# schemathic.net
KiCad netlist of a schematic drawn in EAGLE
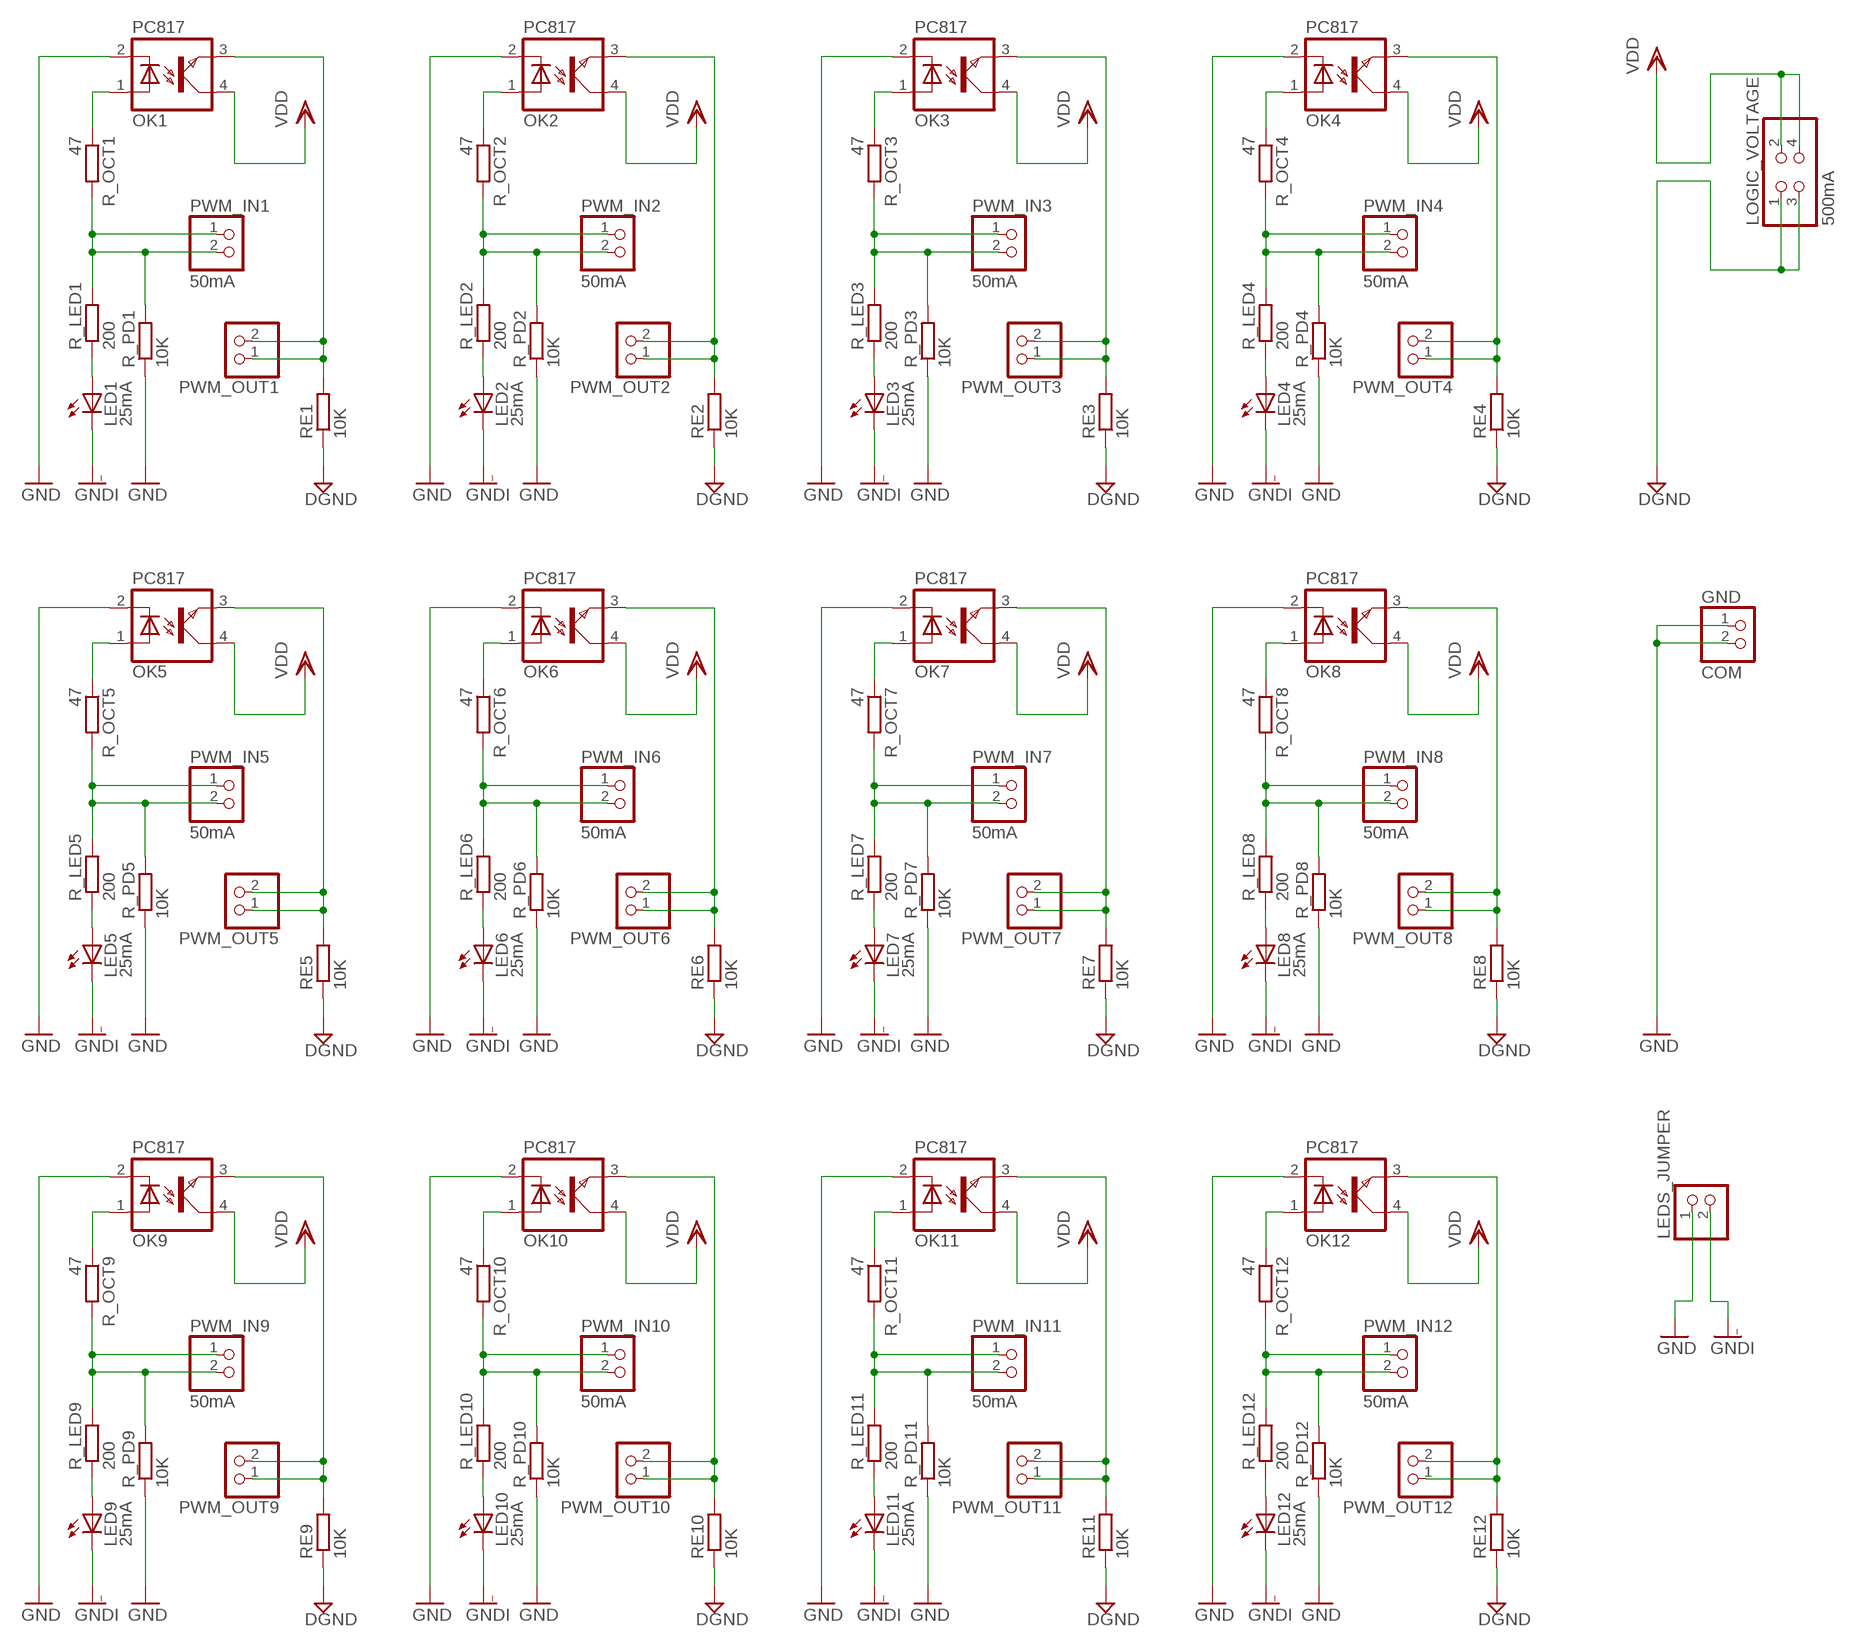
[diagram p0: schematic, sheet 1]

(export (version "E")
  (design (tool "Eeschema 10.0.6"))
  (components
    (comp (ref "GND")
      (value "COM")
      (footprint "eagle-import:1X02")
      (libsource (lib "eagle-import") (part "PINHD-1X2"))
    )
    (comp (ref "LED1")
      (value "25mA")
      (footprint "eagle-import:LED3MM")
      (libsource (lib "eagle-import") (part "LED3MM"))
    )
    (comp (ref "LED2")
      (value "25mA")
      (footprint "eagle-import:LED3MM")
      (libsource (lib "eagle-import") (part "LED3MM"))
    )
    (comp (ref "LED3")
      (value "25mA")
      (footprint "eagle-import:LED3MM")
      (libsource (lib "eagle-import") (part "LED3MM"))
    )
    (comp (ref "LED4")
      (value "25mA")
      (footprint "eagle-import:LED3MM")
      (libsource (lib "eagle-import") (part "LED3MM"))
    )
    (comp (ref "LED5")
      (value "25mA")
      (footprint "eagle-import:LED3MM")
      (libsource (lib "eagle-import") (part "LED3MM"))
    )
    (comp (ref "LED6")
      (value "25mA")
      (footprint "eagle-import:LED3MM")
      (libsource (lib "eagle-import") (part "LED3MM"))
    )
    (comp (ref "LED7")
      (value "25mA")
      (footprint "eagle-import:LED3MM")
      (libsource (lib "eagle-import") (part "LED3MM"))
    )
    (comp (ref "LED8")
      (value "25mA")
      (footprint "eagle-import:LED3MM")
      (libsource (lib "eagle-import") (part "LED3MM"))
    )
    (comp (ref "LED9")
      (value "25mA")
      (footprint "eagle-import:LED3MM")
      (libsource (lib "eagle-import") (part "LED3MM"))
    )
    (comp (ref "LED10")
      (value "25mA")
      (footprint "eagle-import:LED3MM")
      (libsource (lib "eagle-import") (part "LED3MM"))
    )
    (comp (ref "LED11")
      (value "25mA")
      (footprint "eagle-import:LED3MM")
      (libsource (lib "eagle-import") (part "LED3MM"))
    )
    (comp (ref "LED12")
      (value "25mA")
      (footprint "eagle-import:LED3MM")
      (libsource (lib "eagle-import") (part "LED3MM"))
    )
    (comp (ref "LEDS_JUMPER")
      (value "PINHD-1X2")
      (footprint "eagle-import:1X02")
      (libsource (lib "eagle-import") (part "PINHD-1X2"))
    )
    (comp (ref "LOGIC_VOLTAGE")
      (value "500mA")
      (footprint "eagle-import:2X02")
      (libsource (lib "eagle-import") (part "PINHD-2X2"))
    )
    (comp (ref "OK1")
      (value "PC817")
      (footprint "eagle-import:DIL04")
      (fields (field (name "MPN") "PC817X4J000F"))
      (libsource (lib "eagle-import") (part "PC817"))
    )
    (comp (ref "OK2")
      (value "PC817")
      (footprint "eagle-import:DIL04")
      (fields (field (name "MPN") "PC817X4J000F"))
      (libsource (lib "eagle-import") (part "PC817"))
    )
    (comp (ref "OK3")
      (value "PC817")
      (footprint "eagle-import:DIL04")
      (fields (field (name "MPN") "PC817X4J000F"))
      (libsource (lib "eagle-import") (part "PC817"))
    )
    (comp (ref "OK4")
      (value "PC817")
      (footprint "eagle-import:DIL04")
      (fields (field (name "MPN") "PC817X4J000F"))
      (libsource (lib "eagle-import") (part "PC817"))
    )
    (comp (ref "OK5")
      (value "PC817")
      (footprint "eagle-import:DIL04")
      (fields (field (name "MPN") "PC817X4J000F"))
      (libsource (lib "eagle-import") (part "PC817"))
    )
    (comp (ref "OK6")
      (value "PC817")
      (footprint "eagle-import:DIL04")
      (fields (field (name "MPN") "PC817X4J000F"))
      (libsource (lib "eagle-import") (part "PC817"))
    )
    (comp (ref "OK7")
      (value "PC817")
      (footprint "eagle-import:DIL04")
      (fields (field (name "MPN") "PC817X4J000F"))
      (libsource (lib "eagle-import") (part "PC817"))
    )
    (comp (ref "OK8")
      (value "PC817")
      (footprint "eagle-import:DIL04")
      (fields (field (name "MPN") "PC817X4J000F"))
      (libsource (lib "eagle-import") (part "PC817"))
    )
    (comp (ref "OK9")
      (value "PC817")
      (footprint "eagle-import:DIL04")
      (fields (field (name "MPN") "PC817X4J000F"))
      (libsource (lib "eagle-import") (part "PC817"))
    )
    (comp (ref "OK10")
      (value "PC817")
      (footprint "eagle-import:DIL04")
      (fields (field (name "MPN") "PC817X4J000F"))
      (libsource (lib "eagle-import") (part "PC817"))
    )
    (comp (ref "OK11")
      (value "PC817")
      (footprint "eagle-import:DIL04")
      (fields (field (name "MPN") "PC817X4J000F"))
      (libsource (lib "eagle-import") (part "PC817"))
    )
    (comp (ref "OK12")
      (value "PC817")
      (footprint "eagle-import:DIL04")
      (fields (field (name "MPN") "PC817X4J000F"))
      (libsource (lib "eagle-import") (part "PC817"))
    )
    (comp (ref "PWM_IN1")
      (value "50mA")
      (footprint "eagle-import:1X02")
      (libsource (lib "eagle-import") (part "PINHD-1X2"))
    )
    (comp (ref "PWM_IN2")
      (value "50mA")
      (footprint "eagle-import:1X02")
      (libsource (lib "eagle-import") (part "PINHD-1X2"))
    )
    (comp (ref "PWM_IN3")
      (value "50mA")
      (footprint "eagle-import:1X02")
      (libsource (lib "eagle-import") (part "PINHD-1X2"))
    )
    (comp (ref "PWM_IN4")
      (value "50mA")
      (footprint "eagle-import:1X02")
      (libsource (lib "eagle-import") (part "PINHD-1X2"))
    )
    (comp (ref "PWM_IN5")
      (value "50mA")
      (footprint "eagle-import:1X02")
      (libsource (lib "eagle-import") (part "PINHD-1X2"))
    )
    (comp (ref "PWM_IN6")
      (value "50mA")
      (footprint "eagle-import:1X02")
      (libsource (lib "eagle-import") (part "PINHD-1X2"))
    )
    (comp (ref "PWM_IN7")
      (value "50mA")
      (footprint "eagle-import:1X02")
      (libsource (lib "eagle-import") (part "PINHD-1X2"))
    )
    (comp (ref "PWM_IN8")
      (value "50mA")
      (footprint "eagle-import:1X02")
      (libsource (lib "eagle-import") (part "PINHD-1X2"))
    )
    (comp (ref "PWM_IN9")
      (value "50mA")
      (footprint "eagle-import:1X02")
      (libsource (lib "eagle-import") (part "PINHD-1X2"))
    )
    (comp (ref "PWM_IN10")
      (value "50mA")
      (footprint "eagle-import:1X02")
      (libsource (lib "eagle-import") (part "PINHD-1X2"))
    )
    (comp (ref "PWM_IN11")
      (value "50mA")
      (footprint "eagle-import:1X02")
      (libsource (lib "eagle-import") (part "PINHD-1X2"))
    )
    (comp (ref "PWM_IN12")
      (value "50mA")
      (footprint "eagle-import:1X02")
      (libsource (lib "eagle-import") (part "PINHD-1X2"))
    )
    (comp (ref "PWM_OUT1")
      (value "PINHD-1X2")
      (footprint "eagle-import:1X02")
      (libsource (lib "eagle-import") (part "PINHD-1X2"))
    )
    (comp (ref "PWM_OUT2")
      (value "PINHD-1X2")
      (footprint "eagle-import:1X02")
      (libsource (lib "eagle-import") (part "PINHD-1X2"))
    )
    (comp (ref "PWM_OUT3")
      (value "PINHD-1X2")
      (footprint "eagle-import:1X02")
      (libsource (lib "eagle-import") (part "PINHD-1X2"))
    )
    (comp (ref "PWM_OUT4")
      (value "PINHD-1X2")
      (footprint "eagle-import:1X02")
      (libsource (lib "eagle-import") (part "PINHD-1X2"))
    )
    (comp (ref "PWM_OUT5")
      (value "PINHD-1X2")
      (footprint "eagle-import:1X02")
      (libsource (lib "eagle-import") (part "PINHD-1X2"))
    )
    (comp (ref "PWM_OUT6")
      (value "PINHD-1X2")
      (footprint "eagle-import:1X02")
      (libsource (lib "eagle-import") (part "PINHD-1X2"))
    )
    (comp (ref "PWM_OUT7")
      (value "PINHD-1X2")
      (footprint "eagle-import:1X02")
      (libsource (lib "eagle-import") (part "PINHD-1X2"))
    )
    (comp (ref "PWM_OUT8")
      (value "PINHD-1X2")
      (footprint "eagle-import:1X02")
      (libsource (lib "eagle-import") (part "PINHD-1X2"))
    )
    (comp (ref "PWM_OUT9")
      (value "PINHD-1X2")
      (footprint "eagle-import:1X02")
      (libsource (lib "eagle-import") (part "PINHD-1X2"))
    )
    (comp (ref "PWM_OUT10")
      (value "PINHD-1X2")
      (footprint "eagle-import:1X02")
      (libsource (lib "eagle-import") (part "PINHD-1X2"))
    )
    (comp (ref "PWM_OUT11")
      (value "PINHD-1X2")
      (footprint "eagle-import:1X02")
      (libsource (lib "eagle-import") (part "PINHD-1X2"))
    )
    (comp (ref "PWM_OUT12")
      (value "PINHD-1X2")
      (footprint "eagle-import:1X02")
      (libsource (lib "eagle-import") (part "PINHD-1X2"))
    )
    (comp (ref "RE1")
      (value "10K")
      (footprint "eagle-import:0204_7")
      (libsource (lib "eagle-import") (part "R-EU_0204/7"))
    )
    (comp (ref "RE2")
      (value "10K")
      (footprint "eagle-import:0204_7")
      (libsource (lib "eagle-import") (part "R-EU_0204/7"))
    )
    (comp (ref "RE3")
      (value "10K")
      (footprint "eagle-import:0204_7")
      (libsource (lib "eagle-import") (part "R-EU_0204/7"))
    )
    (comp (ref "RE4")
      (value "10K")
      (footprint "eagle-import:0204_7")
      (libsource (lib "eagle-import") (part "R-EU_0204/7"))
    )
    (comp (ref "RE5")
      (value "10K")
      (footprint "eagle-import:0204_7")
      (libsource (lib "eagle-import") (part "R-EU_0204/7"))
    )
    (comp (ref "RE6")
      (value "10K")
      (footprint "eagle-import:0204_7")
      (libsource (lib "eagle-import") (part "R-EU_0204/7"))
    )
    (comp (ref "RE7")
      (value "10K")
      (footprint "eagle-import:0204_7")
      (libsource (lib "eagle-import") (part "R-EU_0204/7"))
    )
    (comp (ref "RE8")
      (value "10K")
      (footprint "eagle-import:0204_7")
      (libsource (lib "eagle-import") (part "R-EU_0204/7"))
    )
    (comp (ref "RE9")
      (value "10K")
      (footprint "eagle-import:0204_7")
      (libsource (lib "eagle-import") (part "R-EU_0204/7"))
    )
    (comp (ref "RE10")
      (value "10K")
      (footprint "eagle-import:0204_7")
      (libsource (lib "eagle-import") (part "R-EU_0204/7"))
    )
    (comp (ref "RE11")
      (value "10K")
      (footprint "eagle-import:0204_7")
      (libsource (lib "eagle-import") (part "R-EU_0204/7"))
    )
    (comp (ref "RE12")
      (value "10K")
      (footprint "eagle-import:0204_7")
      (libsource (lib "eagle-import") (part "R-EU_0204/7"))
    )
    (comp (ref "R_LED1")
      (value "200")
      (footprint "eagle-import:0204_7")
      (libsource (lib "eagle-import") (part "R-EU_0204/7"))
    )
    (comp (ref "R_LED2")
      (value "200")
      (footprint "eagle-import:0204_7")
      (libsource (lib "eagle-import") (part "R-EU_0204/7"))
    )
    (comp (ref "R_LED3")
      (value "200")
      (footprint "eagle-import:0204_7")
      (libsource (lib "eagle-import") (part "R-EU_0204/7"))
    )
    (comp (ref "R_LED4")
      (value "200")
      (footprint "eagle-import:0204_7")
      (libsource (lib "eagle-import") (part "R-EU_0204/7"))
    )
    (comp (ref "R_LED5")
      (value "200")
      (footprint "eagle-import:0204_7")
      (libsource (lib "eagle-import") (part "R-EU_0204/7"))
    )
    (comp (ref "R_LED6")
      (value "200")
      (footprint "eagle-import:0204_7")
      (libsource (lib "eagle-import") (part "R-EU_0204/7"))
    )
    (comp (ref "R_LED7")
      (value "200")
      (footprint "eagle-import:0204_7")
      (libsource (lib "eagle-import") (part "R-EU_0204/7"))
    )
    (comp (ref "R_LED8")
      (value "200")
      (footprint "eagle-import:0204_7")
      (libsource (lib "eagle-import") (part "R-EU_0204/7"))
    )
    (comp (ref "R_LED9")
      (value "200")
      (footprint "eagle-import:0204_7")
      (libsource (lib "eagle-import") (part "R-EU_0204/7"))
    )
    (comp (ref "R_LED10")
      (value "200")
      (footprint "eagle-import:0204_7")
      (libsource (lib "eagle-import") (part "R-EU_0204/7"))
    )
    (comp (ref "R_LED11")
      (value "200")
      (footprint "eagle-import:0204_7")
      (libsource (lib "eagle-import") (part "R-EU_0204/7"))
    )
    (comp (ref "R_LED12")
      (value "200")
      (footprint "eagle-import:0204_7")
      (libsource (lib "eagle-import") (part "R-EU_0204/7"))
    )
    (comp (ref "R_OCT1")
      (value "47")
      (footprint "eagle-import:0204_7")
      (libsource (lib "eagle-import") (part "R-EU_0204/7"))
    )
    (comp (ref "R_OCT2")
      (value "47")
      (footprint "eagle-import:0204_7")
      (libsource (lib "eagle-import") (part "R-EU_0204/7"))
    )
    (comp (ref "R_OCT3")
      (value "47")
      (footprint "eagle-import:0204_7")
      (libsource (lib "eagle-import") (part "R-EU_0204/7"))
    )
    (comp (ref "R_OCT4")
      (value "47")
      (footprint "eagle-import:0204_7")
      (libsource (lib "eagle-import") (part "R-EU_0204/7"))
    )
    (comp (ref "R_OCT5")
      (value "47")
      (footprint "eagle-import:0204_7")
      (libsource (lib "eagle-import") (part "R-EU_0204/7"))
    )
    (comp (ref "R_OCT6")
      (value "47")
      (footprint "eagle-import:0204_7")
      (libsource (lib "eagle-import") (part "R-EU_0204/7"))
    )
    (comp (ref "R_OCT7")
      (value "47")
      (footprint "eagle-import:0204_7")
      (libsource (lib "eagle-import") (part "R-EU_0204/7"))
    )
    (comp (ref "R_OCT8")
      (value "47")
      (footprint "eagle-import:0204_7")
      (libsource (lib "eagle-import") (part "R-EU_0204/7"))
    )
    (comp (ref "R_OCT9")
      (value "47")
      (footprint "eagle-import:0204_7")
      (libsource (lib "eagle-import") (part "R-EU_0204/7"))
    )
    (comp (ref "R_OCT10")
      (value "47")
      (footprint "eagle-import:0204_7")
      (libsource (lib "eagle-import") (part "R-EU_0204/7"))
    )
    (comp (ref "R_OCT11")
      (value "47")
      (footprint "eagle-import:0204_7")
      (libsource (lib "eagle-import") (part "R-EU_0204/7"))
    )
    (comp (ref "R_OCT12")
      (value "47")
      (footprint "eagle-import:0204_7")
      (libsource (lib "eagle-import") (part "R-EU_0204/7"))
    )
    (comp (ref "R_PD1")
      (value "10K")
      (footprint "eagle-import:0204_7")
      (libsource (lib "eagle-import") (part "R-EU_0204/7"))
    )
    (comp (ref "R_PD2")
      (value "10K")
      (footprint "eagle-import:0204_7")
      (libsource (lib "eagle-import") (part "R-EU_0204/7"))
    )
    (comp (ref "R_PD3")
      (value "10K")
      (footprint "eagle-import:0204_7")
      (libsource (lib "eagle-import") (part "R-EU_0204/7"))
    )
    (comp (ref "R_PD4")
      (value "10K")
      (footprint "eagle-import:0204_7")
      (libsource (lib "eagle-import") (part "R-EU_0204/7"))
    )
    (comp (ref "R_PD5")
      (value "10K")
      (footprint "eagle-import:0204_7")
      (libsource (lib "eagle-import") (part "R-EU_0204/7"))
    )
    (comp (ref "R_PD6")
      (value "10K")
      (footprint "eagle-import:0204_7")
      (libsource (lib "eagle-import") (part "R-EU_0204/7"))
    )
    (comp (ref "R_PD7")
      (value "10K")
      (footprint "eagle-import:0204_7")
      (libsource (lib "eagle-import") (part "R-EU_0204/7"))
    )
    (comp (ref "R_PD8")
      (value "10K")
      (footprint "eagle-import:0204_7")
      (libsource (lib "eagle-import") (part "R-EU_0204/7"))
    )
    (comp (ref "R_PD9")
      (value "10K")
      (footprint "eagle-import:0204_7")
      (libsource (lib "eagle-import") (part "R-EU_0204/7"))
    )
    (comp (ref "R_PD10")
      (value "10K")
      (footprint "eagle-import:0204_7")
      (libsource (lib "eagle-import") (part "R-EU_0204/7"))
    )
    (comp (ref "R_PD11")
      (value "10K")
      (footprint "eagle-import:0204_7")
      (libsource (lib "eagle-import") (part "R-EU_0204/7"))
    )
    (comp (ref "R_PD12")
      (value "10K")
      (footprint "eagle-import:0204_7")
      (libsource (lib "eagle-import") (part "R-EU_0204/7"))
    )
  )
  (nets
    (net (code "1") (name "DGND") (class "Default")
      (node (ref "LOGIC_VOLTAGE") (pin "1") (pinfunction "1_1") (pintype "passive"))
      (node (ref "LOGIC_VOLTAGE") (pin "3") (pinfunction "3_3") (pintype "passive"))
      (node (ref "RE1") (pin "1") (pinfunction "1_1") (pintype "passive"))
      (node (ref "RE10") (pin "1") (pinfunction "1_1") (pintype "passive"))
      (node (ref "RE11") (pin "1") (pinfunction "1_1") (pintype "passive"))
      (node (ref "RE12") (pin "1") (pinfunction "1_1") (pintype "passive"))
      (node (ref "RE2") (pin "1") (pinfunction "1_1") (pintype "passive"))
      (node (ref "RE3") (pin "1") (pinfunction "1_1") (pintype "passive"))
      (node (ref "RE4") (pin "1") (pinfunction "1_1") (pintype "passive"))
      (node (ref "RE5") (pin "1") (pinfunction "1_1") (pintype "passive"))
      (node (ref "RE6") (pin "1") (pinfunction "1_1") (pintype "passive"))
      (node (ref "RE7") (pin "1") (pinfunction "1_1") (pintype "passive"))
      (node (ref "RE8") (pin "1") (pinfunction "1_1") (pintype "passive"))
      (node (ref "RE9") (pin "1") (pinfunction "1_1") (pintype "passive"))
    )
    (net (code "2") (name "GND") (class "Default")
      (node (ref "GND") (pin "1") (pinfunction "1_1") (pintype "passive"))
      (node (ref "GND") (pin "2") (pinfunction "2_2") (pintype "passive"))
      (node (ref "LEDS_JUMPER") (pin "1") (pinfunction "1_1") (pintype "passive"))
      (node (ref "OK1") (pin "2") (pinfunction "C_2") (pintype "passive"))
      (node (ref "OK10") (pin "2") (pinfunction "C_2") (pintype "passive"))
      (node (ref "OK11") (pin "2") (pinfunction "C_2") (pintype "passive"))
      (node (ref "OK12") (pin "2") (pinfunction "C_2") (pintype "passive"))
      (node (ref "OK2") (pin "2") (pinfunction "C_2") (pintype "passive"))
      (node (ref "OK3") (pin "2") (pinfunction "C_2") (pintype "passive"))
      (node (ref "OK4") (pin "2") (pinfunction "C_2") (pintype "passive"))
      (node (ref "OK5") (pin "2") (pinfunction "C_2") (pintype "passive"))
      (node (ref "OK6") (pin "2") (pinfunction "C_2") (pintype "passive"))
      (node (ref "OK7") (pin "2") (pinfunction "C_2") (pintype "passive"))
      (node (ref "OK8") (pin "2") (pinfunction "C_2") (pintype "passive"))
      (node (ref "OK9") (pin "2") (pinfunction "C_2") (pintype "passive"))
      (node (ref "R_PD1") (pin "1") (pinfunction "1_1") (pintype "passive"))
      (node (ref "R_PD10") (pin "1") (pinfunction "1_1") (pintype "passive"))
      (node (ref "R_PD11") (pin "1") (pinfunction "1_1") (pintype "passive"))
      (node (ref "R_PD12") (pin "1") (pinfunction "1_1") (pintype "passive"))
      (node (ref "R_PD2") (pin "1") (pinfunction "1_1") (pintype "passive"))
      (node (ref "R_PD3") (pin "1") (pinfunction "1_1") (pintype "passive"))
      (node (ref "R_PD4") (pin "1") (pinfunction "1_1") (pintype "passive"))
      (node (ref "R_PD5") (pin "1") (pinfunction "1_1") (pintype "passive"))
      (node (ref "R_PD6") (pin "1") (pinfunction "1_1") (pintype "passive"))
      (node (ref "R_PD7") (pin "1") (pinfunction "1_1") (pintype "passive"))
      (node (ref "R_PD8") (pin "1") (pinfunction "1_1") (pintype "passive"))
      (node (ref "R_PD9") (pin "1") (pinfunction "1_1") (pintype "passive"))
    )
    (net (code "3") (name "GNDI") (class "Default")
      (node (ref "LED1") (pin "K") (pinfunction "C_K") (pintype "passive"))
      (node (ref "LED10") (pin "K") (pinfunction "C_K") (pintype "passive"))
      (node (ref "LED11") (pin "K") (pinfunction "C_K") (pintype "passive"))
      (node (ref "LED12") (pin "K") (pinfunction "C_K") (pintype "passive"))
      (node (ref "LED2") (pin "K") (pinfunction "C_K") (pintype "passive"))
      (node (ref "LED3") (pin "K") (pinfunction "C_K") (pintype "passive"))
      (node (ref "LED4") (pin "K") (pinfunction "C_K") (pintype "passive"))
      (node (ref "LED5") (pin "K") (pinfunction "C_K") (pintype "passive"))
      (node (ref "LED6") (pin "K") (pinfunction "C_K") (pintype "passive"))
      (node (ref "LED7") (pin "K") (pinfunction "C_K") (pintype "passive"))
      (node (ref "LED8") (pin "K") (pinfunction "C_K") (pintype "passive"))
      (node (ref "LED9") (pin "K") (pinfunction "C_K") (pintype "passive"))
      (node (ref "LEDS_JUMPER") (pin "2") (pinfunction "2_2") (pintype "passive"))
    )
    (net (code "4") (name "Net-(LED1-PadA)") (class "Default")
      (node (ref "LED1") (pin "A") (pinfunction "A_A") (pintype "passive"))
      (node (ref "R_LED1") (pin "1") (pinfunction "1_1") (pintype "passive"))
    )
    (net (code "5") (name "Net-(LED2-PadA)") (class "Default")
      (node (ref "LED2") (pin "A") (pinfunction "A_A") (pintype "passive"))
      (node (ref "R_LED2") (pin "1") (pinfunction "1_1") (pintype "passive"))
    )
    (net (code "6") (name "Net-(LED3-PadA)") (class "Default")
      (node (ref "LED3") (pin "A") (pinfunction "A_A") (pintype "passive"))
      (node (ref "R_LED3") (pin "1") (pinfunction "1_1") (pintype "passive"))
    )
    (net (code "7") (name "Net-(LED4-PadA)") (class "Default")
      (node (ref "LED4") (pin "A") (pinfunction "A_A") (pintype "passive"))
      (node (ref "R_LED4") (pin "1") (pinfunction "1_1") (pintype "passive"))
    )
    (net (code "8") (name "Net-(LED5-PadA)") (class "Default")
      (node (ref "LED5") (pin "A") (pinfunction "A_A") (pintype "passive"))
      (node (ref "R_LED5") (pin "1") (pinfunction "1_1") (pintype "passive"))
    )
    (net (code "9") (name "Net-(LED6-PadA)") (class "Default")
      (node (ref "LED6") (pin "A") (pinfunction "A_A") (pintype "passive"))
      (node (ref "R_LED6") (pin "1") (pinfunction "1_1") (pintype "passive"))
    )
    (net (code "10") (name "Net-(LED7-PadA)") (class "Default")
      (node (ref "LED7") (pin "A") (pinfunction "A_A") (pintype "passive"))
      (node (ref "R_LED7") (pin "1") (pinfunction "1_1") (pintype "passive"))
    )
    (net (code "11") (name "Net-(LED8-PadA)") (class "Default")
      (node (ref "LED8") (pin "A") (pinfunction "A_A") (pintype "passive"))
      (node (ref "R_LED8") (pin "1") (pinfunction "1_1") (pintype "passive"))
    )
    (net (code "12") (name "Net-(LED9-PadA)") (class "Default")
      (node (ref "LED9") (pin "A") (pinfunction "A_A") (pintype "passive"))
      (node (ref "R_LED9") (pin "1") (pinfunction "1_1") (pintype "passive"))
    )
    (net (code "13") (name "Net-(LED10-PadA)") (class "Default")
      (node (ref "LED10") (pin "A") (pinfunction "A_A") (pintype "passive"))
      (node (ref "R_LED10") (pin "1") (pinfunction "1_1") (pintype "passive"))
    )
    (net (code "14") (name "Net-(LED11-PadA)") (class "Default")
      (node (ref "LED11") (pin "A") (pinfunction "A_A") (pintype "passive"))
      (node (ref "R_LED11") (pin "1") (pinfunction "1_1") (pintype "passive"))
    )
    (net (code "15") (name "Net-(LED12-PadA)") (class "Default")
      (node (ref "LED12") (pin "A") (pinfunction "A_A") (pintype "passive"))
      (node (ref "R_LED12") (pin "1") (pinfunction "1_1") (pintype "passive"))
    )
    (net (code "16") (name "Net-(OK1-A)") (class "Default")
      (node (ref "OK1") (pin "1") (pinfunction "A_1") (pintype "passive"))
      (node (ref "R_OCT1") (pin "1") (pinfunction "1_1") (pintype "passive"))
    )
    (net (code "17") (name "Net-(OK1-EMIT)") (class "Default")
      (node (ref "OK1") (pin "3") (pinfunction "EMIT_3") (pintype "passive"))
      (node (ref "PWM_OUT1") (pin "1") (pinfunction "1_1") (pintype "passive"))
      (node (ref "PWM_OUT1") (pin "2") (pinfunction "2_2") (pintype "passive"))
      (node (ref "RE1") (pin "2") (pinfunction "2_2") (pintype "passive"))
    )
    (net (code "18") (name "Net-(OK2-A)") (class "Default")
      (node (ref "OK2") (pin "1") (pinfunction "A_1") (pintype "passive"))
      (node (ref "R_OCT2") (pin "1") (pinfunction "1_1") (pintype "passive"))
    )
    (net (code "19") (name "Net-(OK2-EMIT)") (class "Default")
      (node (ref "OK2") (pin "3") (pinfunction "EMIT_3") (pintype "passive"))
      (node (ref "PWM_OUT2") (pin "1") (pinfunction "1_1") (pintype "passive"))
      (node (ref "PWM_OUT2") (pin "2") (pinfunction "2_2") (pintype "passive"))
      (node (ref "RE2") (pin "2") (pinfunction "2_2") (pintype "passive"))
    )
    (net (code "20") (name "Net-(OK3-A)") (class "Default")
      (node (ref "OK3") (pin "1") (pinfunction "A_1") (pintype "passive"))
      (node (ref "R_OCT3") (pin "1") (pinfunction "1_1") (pintype "passive"))
    )
    (net (code "21") (name "Net-(OK3-EMIT)") (class "Default")
      (node (ref "OK3") (pin "3") (pinfunction "EMIT_3") (pintype "passive"))
      (node (ref "PWM_OUT3") (pin "1") (pinfunction "1_1") (pintype "passive"))
      (node (ref "PWM_OUT3") (pin "2") (pinfunction "2_2") (pintype "passive"))
      (node (ref "RE3") (pin "2") (pinfunction "2_2") (pintype "passive"))
    )
    (net (code "22") (name "Net-(OK4-A)") (class "Default")
      (node (ref "OK4") (pin "1") (pinfunction "A_1") (pintype "passive"))
      (node (ref "R_OCT4") (pin "1") (pinfunction "1_1") (pintype "passive"))
    )
    (net (code "23") (name "Net-(OK4-EMIT)") (class "Default")
      (node (ref "OK4") (pin "3") (pinfunction "EMIT_3") (pintype "passive"))
      (node (ref "PWM_OUT4") (pin "1") (pinfunction "1_1") (pintype "passive"))
      (node (ref "PWM_OUT4") (pin "2") (pinfunction "2_2") (pintype "passive"))
      (node (ref "RE4") (pin "2") (pinfunction "2_2") (pintype "passive"))
    )
    (net (code "24") (name "Net-(OK5-A)") (class "Default")
      (node (ref "OK5") (pin "1") (pinfunction "A_1") (pintype "passive"))
      (node (ref "R_OCT5") (pin "1") (pinfunction "1_1") (pintype "passive"))
    )
    (net (code "25") (name "Net-(OK5-EMIT)") (class "Default")
      (node (ref "OK5") (pin "3") (pinfunction "EMIT_3") (pintype "passive"))
      (node (ref "PWM_OUT5") (pin "1") (pinfunction "1_1") (pintype "passive"))
      (node (ref "PWM_OUT5") (pin "2") (pinfunction "2_2") (pintype "passive"))
      (node (ref "RE5") (pin "2") (pinfunction "2_2") (pintype "passive"))
    )
    (net (code "26") (name "Net-(OK6-A)") (class "Default")
      (node (ref "OK6") (pin "1") (pinfunction "A_1") (pintype "passive"))
      (node (ref "R_OCT6") (pin "1") (pinfunction "1_1") (pintype "passive"))
    )
    (net (code "27") (name "Net-(OK6-EMIT)") (class "Default")
      (node (ref "OK6") (pin "3") (pinfunction "EMIT_3") (pintype "passive"))
      (node (ref "PWM_OUT6") (pin "1") (pinfunction "1_1") (pintype "passive"))
      (node (ref "PWM_OUT6") (pin "2") (pinfunction "2_2") (pintype "passive"))
      (node (ref "RE6") (pin "2") (pinfunction "2_2") (pintype "passive"))
    )
    (net (code "28") (name "Net-(OK7-A)") (class "Default")
      (node (ref "OK7") (pin "1") (pinfunction "A_1") (pintype "passive"))
      (node (ref "R_OCT7") (pin "1") (pinfunction "1_1") (pintype "passive"))
    )
    (net (code "29") (name "Net-(OK7-EMIT)") (class "Default")
      (node (ref "OK7") (pin "3") (pinfunction "EMIT_3") (pintype "passive"))
      (node (ref "PWM_OUT7") (pin "1") (pinfunction "1_1") (pintype "passive"))
      (node (ref "PWM_OUT7") (pin "2") (pinfunction "2_2") (pintype "passive"))
      (node (ref "RE7") (pin "2") (pinfunction "2_2") (pintype "passive"))
    )
    (net (code "30") (name "Net-(OK8-A)") (class "Default")
      (node (ref "OK8") (pin "1") (pinfunction "A_1") (pintype "passive"))
      (node (ref "R_OCT8") (pin "1") (pinfunction "1_1") (pintype "passive"))
    )
    (net (code "31") (name "Net-(OK8-EMIT)") (class "Default")
      (node (ref "OK8") (pin "3") (pinfunction "EMIT_3") (pintype "passive"))
      (node (ref "PWM_OUT8") (pin "1") (pinfunction "1_1") (pintype "passive"))
      (node (ref "PWM_OUT8") (pin "2") (pinfunction "2_2") (pintype "passive"))
      (node (ref "RE8") (pin "2") (pinfunction "2_2") (pintype "passive"))
    )
    (net (code "32") (name "Net-(OK9-A)") (class "Default")
      (node (ref "OK9") (pin "1") (pinfunction "A_1") (pintype "passive"))
      (node (ref "R_OCT9") (pin "1") (pinfunction "1_1") (pintype "passive"))
    )
    (net (code "33") (name "Net-(OK9-EMIT)") (class "Default")
      (node (ref "OK9") (pin "3") (pinfunction "EMIT_3") (pintype "passive"))
      (node (ref "PWM_OUT9") (pin "1") (pinfunction "1_1") (pintype "passive"))
      (node (ref "PWM_OUT9") (pin "2") (pinfunction "2_2") (pintype "passive"))
      (node (ref "RE9") (pin "2") (pinfunction "2_2") (pintype "passive"))
    )
    (net (code "34") (name "Net-(OK10-A)") (class "Default")
      (node (ref "OK10") (pin "1") (pinfunction "A_1") (pintype "passive"))
      (node (ref "R_OCT10") (pin "1") (pinfunction "1_1") (pintype "passive"))
    )
    (net (code "35") (name "Net-(OK10-EMIT)") (class "Default")
      (node (ref "OK10") (pin "3") (pinfunction "EMIT_3") (pintype "passive"))
      (node (ref "PWM_OUT10") (pin "1") (pinfunction "1_1") (pintype "passive"))
      (node (ref "PWM_OUT10") (pin "2") (pinfunction "2_2") (pintype "passive"))
      (node (ref "RE10") (pin "2") (pinfunction "2_2") (pintype "passive"))
    )
    (net (code "36") (name "Net-(OK11-A)") (class "Default")
      (node (ref "OK11") (pin "1") (pinfunction "A_1") (pintype "passive"))
      (node (ref "R_OCT11") (pin "1") (pinfunction "1_1") (pintype "passive"))
    )
    (net (code "37") (name "Net-(OK11-EMIT)") (class "Default")
      (node (ref "OK11") (pin "3") (pinfunction "EMIT_3") (pintype "passive"))
      (node (ref "PWM_OUT11") (pin "1") (pinfunction "1_1") (pintype "passive"))
      (node (ref "PWM_OUT11") (pin "2") (pinfunction "2_2") (pintype "passive"))
      (node (ref "RE11") (pin "2") (pinfunction "2_2") (pintype "passive"))
    )
    (net (code "38") (name "Net-(OK12-A)") (class "Default")
      (node (ref "OK12") (pin "1") (pinfunction "A_1") (pintype "passive"))
      (node (ref "R_OCT12") (pin "1") (pinfunction "1_1") (pintype "passive"))
    )
    (net (code "39") (name "Net-(OK12-EMIT)") (class "Default")
      (node (ref "OK12") (pin "3") (pinfunction "EMIT_3") (pintype "passive"))
      (node (ref "PWM_OUT12") (pin "1") (pinfunction "1_1") (pintype "passive"))
      (node (ref "PWM_OUT12") (pin "2") (pinfunction "2_2") (pintype "passive"))
      (node (ref "RE12") (pin "2") (pinfunction "2_2") (pintype "passive"))
    )
    (net (code "40") (name "Net-(PWM_IN1-Pad1)") (class "Default")
      (node (ref "PWM_IN1") (pin "1") (pinfunction "1_1") (pintype "passive"))
      (node (ref "PWM_IN1") (pin "2") (pinfunction "2_2") (pintype "passive"))
      (node (ref "R_LED1") (pin "2") (pinfunction "2_2") (pintype "passive"))
      (node (ref "R_OCT1") (pin "2") (pinfunction "2_2") (pintype "passive"))
      (node (ref "R_PD1") (pin "2") (pinfunction "2_2") (pintype "passive"))
    )
    (net (code "41") (name "Net-(PWM_IN2-Pad1)") (class "Default")
      (node (ref "PWM_IN2") (pin "1") (pinfunction "1_1") (pintype "passive"))
      (node (ref "PWM_IN2") (pin "2") (pinfunction "2_2") (pintype "passive"))
      (node (ref "R_LED2") (pin "2") (pinfunction "2_2") (pintype "passive"))
      (node (ref "R_OCT2") (pin "2") (pinfunction "2_2") (pintype "passive"))
      (node (ref "R_PD2") (pin "2") (pinfunction "2_2") (pintype "passive"))
    )
    (net (code "42") (name "Net-(PWM_IN3-Pad1)") (class "Default")
      (node (ref "PWM_IN3") (pin "1") (pinfunction "1_1") (pintype "passive"))
      (node (ref "PWM_IN3") (pin "2") (pinfunction "2_2") (pintype "passive"))
      (node (ref "R_LED3") (pin "2") (pinfunction "2_2") (pintype "passive"))
      (node (ref "R_OCT3") (pin "2") (pinfunction "2_2") (pintype "passive"))
      (node (ref "R_PD3") (pin "2") (pinfunction "2_2") (pintype "passive"))
    )
    (net (code "43") (name "Net-(PWM_IN4-Pad1)") (class "Default")
      (node (ref "PWM_IN4") (pin "1") (pinfunction "1_1") (pintype "passive"))
      (node (ref "PWM_IN4") (pin "2") (pinfunction "2_2") (pintype "passive"))
      (node (ref "R_LED4") (pin "2") (pinfunction "2_2") (pintype "passive"))
      (node (ref "R_OCT4") (pin "2") (pinfunction "2_2") (pintype "passive"))
      (node (ref "R_PD4") (pin "2") (pinfunction "2_2") (pintype "passive"))
    )
    (net (code "44") (name "Net-(PWM_IN5-Pad1)") (class "Default")
      (node (ref "PWM_IN5") (pin "1") (pinfunction "1_1") (pintype "passive"))
      (node (ref "PWM_IN5") (pin "2") (pinfunction "2_2") (pintype "passive"))
      (node (ref "R_LED5") (pin "2") (pinfunction "2_2") (pintype "passive"))
      (node (ref "R_OCT5") (pin "2") (pinfunction "2_2") (pintype "passive"))
      (node (ref "R_PD5") (pin "2") (pinfunction "2_2") (pintype "passive"))
    )
    (net (code "45") (name "Net-(PWM_IN6-Pad1)") (class "Default")
      (node (ref "PWM_IN6") (pin "1") (pinfunction "1_1") (pintype "passive"))
      (node (ref "PWM_IN6") (pin "2") (pinfunction "2_2") (pintype "passive"))
      (node (ref "R_LED6") (pin "2") (pinfunction "2_2") (pintype "passive"))
      (node (ref "R_OCT6") (pin "2") (pinfunction "2_2") (pintype "passive"))
      (node (ref "R_PD6") (pin "2") (pinfunction "2_2") (pintype "passive"))
    )
    (net (code "46") (name "Net-(PWM_IN7-Pad1)") (class "Default")
      (node (ref "PWM_IN7") (pin "1") (pinfunction "1_1") (pintype "passive"))
      (node (ref "PWM_IN7") (pin "2") (pinfunction "2_2") (pintype "passive"))
      (node (ref "R_LED7") (pin "2") (pinfunction "2_2") (pintype "passive"))
      (node (ref "R_OCT7") (pin "2") (pinfunction "2_2") (pintype "passive"))
      (node (ref "R_PD7") (pin "2") (pinfunction "2_2") (pintype "passive"))
    )
    (net (code "47") (name "Net-(PWM_IN8-Pad1)") (class "Default")
      (node (ref "PWM_IN8") (pin "1") (pinfunction "1_1") (pintype "passive"))
      (node (ref "PWM_IN8") (pin "2") (pinfunction "2_2") (pintype "passive"))
      (node (ref "R_LED8") (pin "2") (pinfunction "2_2") (pintype "passive"))
      (node (ref "R_OCT8") (pin "2") (pinfunction "2_2") (pintype "passive"))
      (node (ref "R_PD8") (pin "2") (pinfunction "2_2") (pintype "passive"))
    )
    (net (code "48") (name "Net-(PWM_IN9-Pad1)") (class "Default")
      (node (ref "PWM_IN9") (pin "1") (pinfunction "1_1") (pintype "passive"))
      (node (ref "PWM_IN9") (pin "2") (pinfunction "2_2") (pintype "passive"))
      (node (ref "R_LED9") (pin "2") (pinfunction "2_2") (pintype "passive"))
      (node (ref "R_OCT9") (pin "2") (pinfunction "2_2") (pintype "passive"))
      (node (ref "R_PD9") (pin "2") (pinfunction "2_2") (pintype "passive"))
    )
    (net (code "49") (name "Net-(PWM_IN10-Pad1)") (class "Default")
      (node (ref "PWM_IN10") (pin "1") (pinfunction "1_1") (pintype "passive"))
      (node (ref "PWM_IN10") (pin "2") (pinfunction "2_2") (pintype "passive"))
      (node (ref "R_LED10") (pin "2") (pinfunction "2_2") (pintype "passive"))
      (node (ref "R_OCT10") (pin "2") (pinfunction "2_2") (pintype "passive"))
      (node (ref "R_PD10") (pin "2") (pinfunction "2_2") (pintype "passive"))
    )
    (net (code "50") (name "Net-(PWM_IN11-Pad1)") (class "Default")
      (node (ref "PWM_IN11") (pin "1") (pinfunction "1_1") (pintype "passive"))
      (node (ref "PWM_IN11") (pin "2") (pinfunction "2_2") (pintype "passive"))
      (node (ref "R_LED11") (pin "2") (pinfunction "2_2") (pintype "passive"))
      (node (ref "R_OCT11") (pin "2") (pinfunction "2_2") (pintype "passive"))
      (node (ref "R_PD11") (pin "2") (pinfunction "2_2") (pintype "passive"))
    )
    (net (code "51") (name "Net-(PWM_IN12-Pad1)") (class "Default")
      (node (ref "PWM_IN12") (pin "1") (pinfunction "1_1") (pintype "passive"))
      (node (ref "PWM_IN12") (pin "2") (pinfunction "2_2") (pintype "passive"))
      (node (ref "R_LED12") (pin "2") (pinfunction "2_2") (pintype "passive"))
      (node (ref "R_OCT12") (pin "2") (pinfunction "2_2") (pintype "passive"))
      (node (ref "R_PD12") (pin "2") (pinfunction "2_2") (pintype "passive"))
    )
    (net (code "52") (name "VDD") (class "Default")
      (node (ref "LOGIC_VOLTAGE") (pin "2") (pinfunction "2_2") (pintype "passive"))
      (node (ref "LOGIC_VOLTAGE") (pin "4") (pinfunction "4_4") (pintype "passive"))
      (node (ref "OK1") (pin "4") (pinfunction "COL_4") (pintype "passive"))
      (node (ref "OK10") (pin "4") (pinfunction "COL_4") (pintype "passive"))
      (node (ref "OK11") (pin "4") (pinfunction "COL_4") (pintype "passive"))
      (node (ref "OK12") (pin "4") (pinfunction "COL_4") (pintype "passive"))
      (node (ref "OK2") (pin "4") (pinfunction "COL_4") (pintype "passive"))
      (node (ref "OK3") (pin "4") (pinfunction "COL_4") (pintype "passive"))
      (node (ref "OK4") (pin "4") (pinfunction "COL_4") (pintype "passive"))
      (node (ref "OK5") (pin "4") (pinfunction "COL_4") (pintype "passive"))
      (node (ref "OK6") (pin "4") (pinfunction "COL_4") (pintype "passive"))
      (node (ref "OK7") (pin "4") (pinfunction "COL_4") (pintype "passive"))
      (node (ref "OK8") (pin "4") (pinfunction "COL_4") (pintype "passive"))
      (node (ref "OK9") (pin "4") (pinfunction "COL_4") (pintype "passive"))
    )
  )
)
